# gearshift_controller.net
KiCad netlist of a schematic drawn in EAGLE
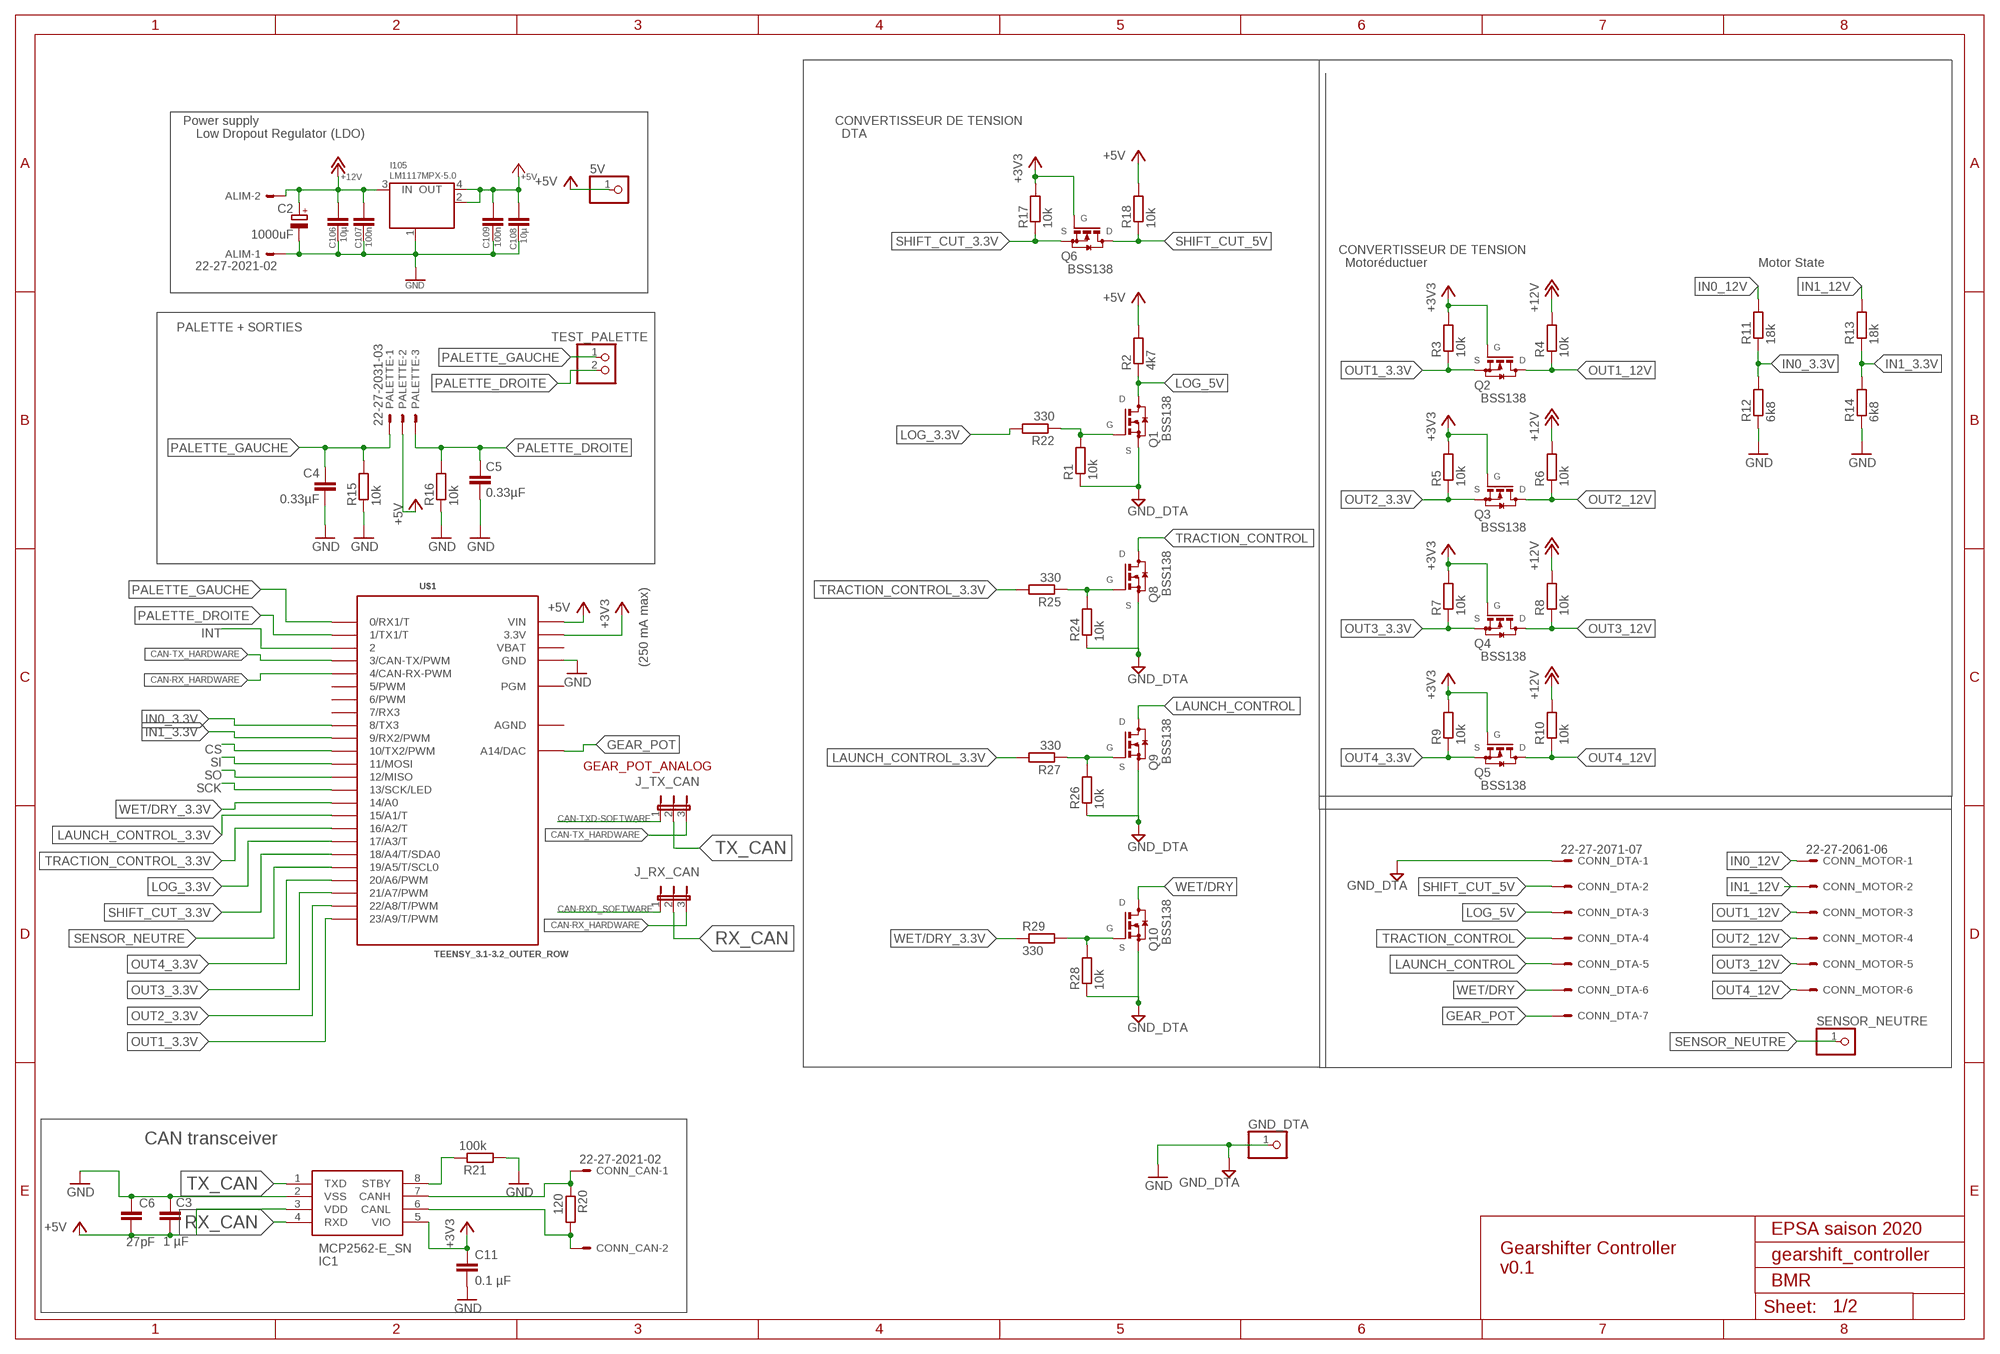
[diagram p0: schematic, sheet 1]
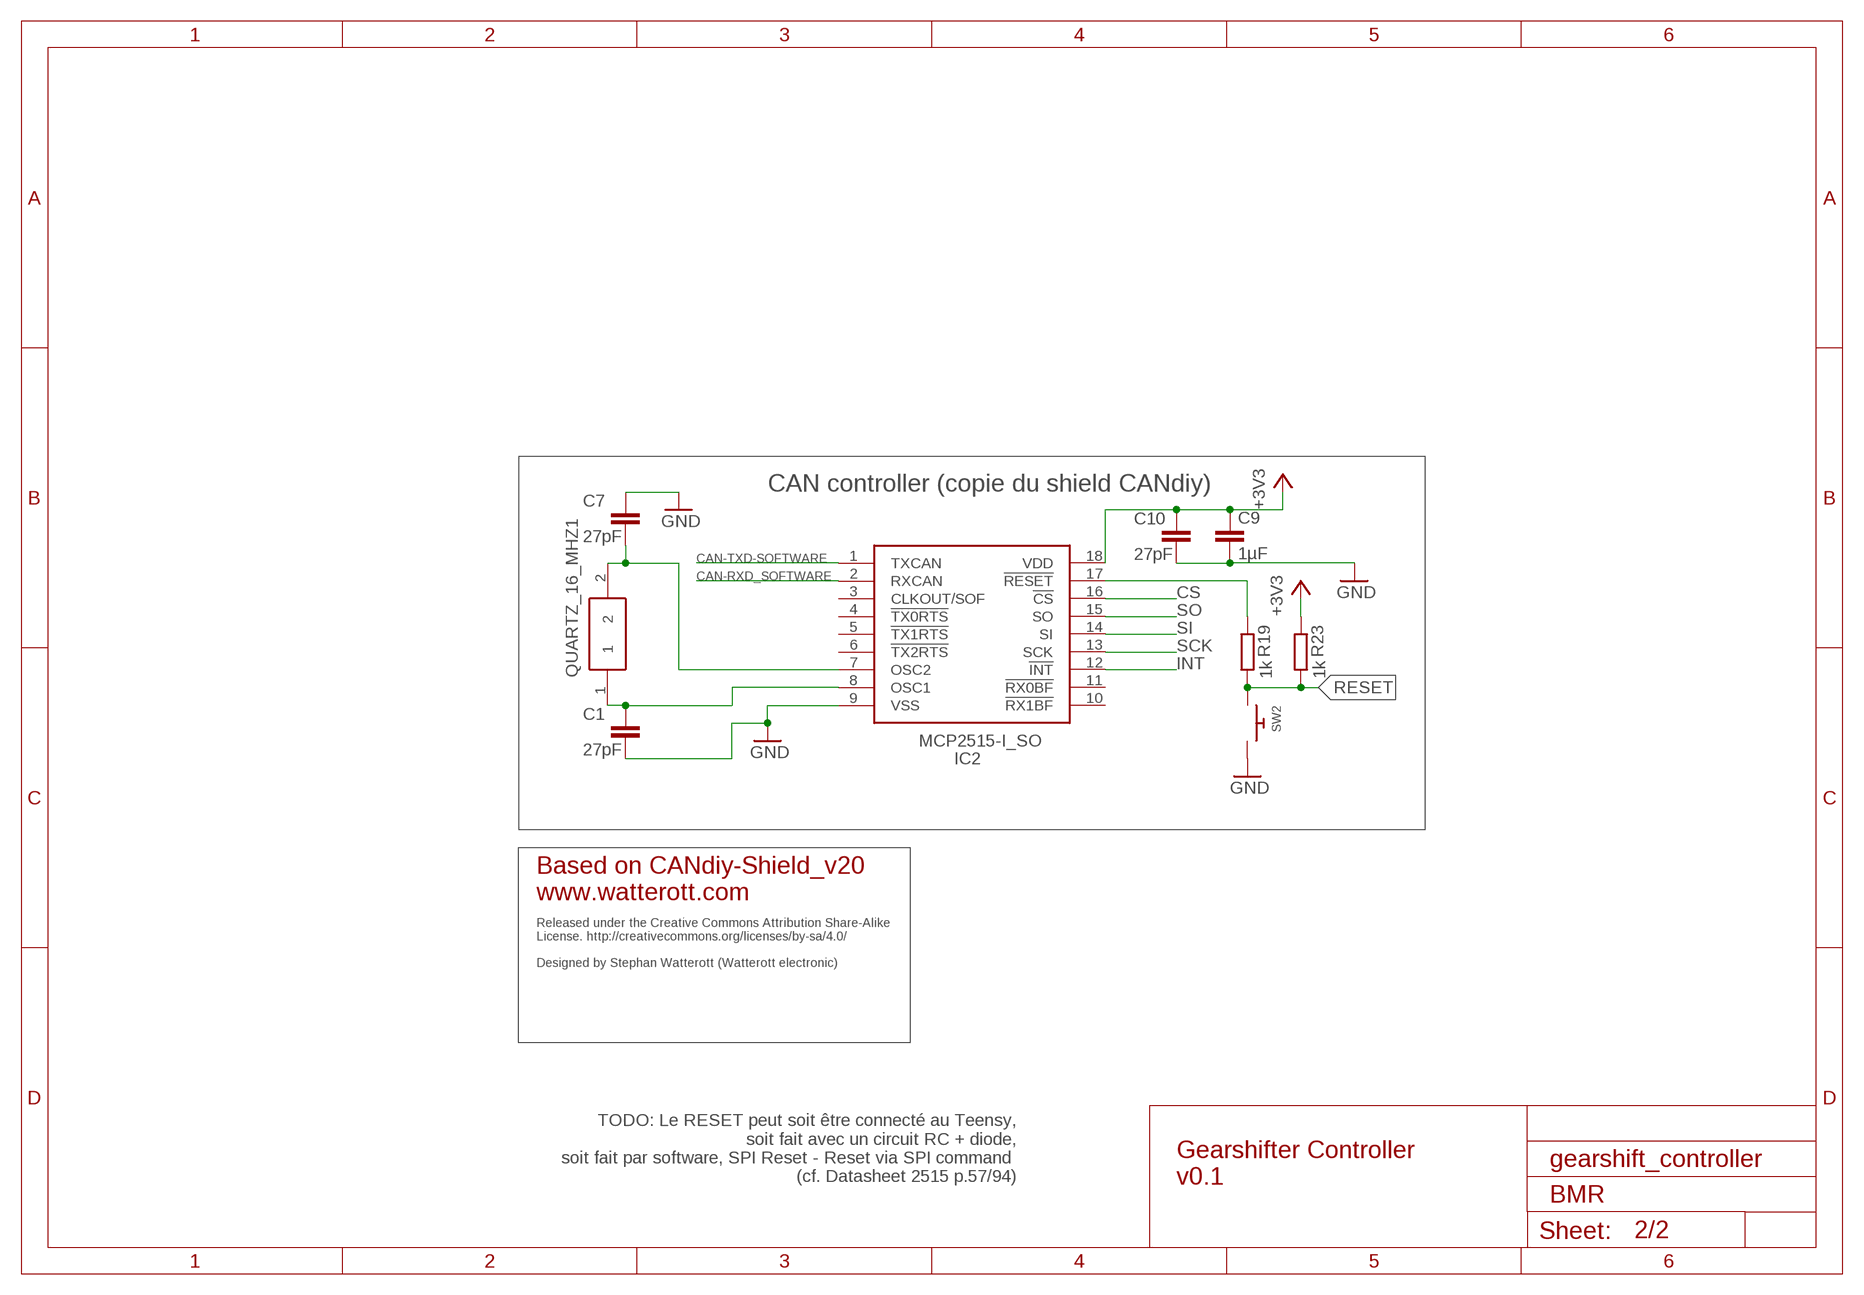
[diagram p1: schematic, sheet 2]

(export (version "E")
  (design (tool "Eeschema 10.0.6"))
  (components
    (comp (ref "C1")
      (value "27pF")
      (footprint "eagle-import:C0805")
      (libsource (lib "eagle-import") (part "rcl_334_C-EUC0805"))
    )
    (comp (ref "C7")
      (value "27pF")
      (footprint "eagle-import:C0805")
      (libsource (lib "eagle-import") (part "rcl_334_C-EUC0805"))
    )
    (comp (ref "C9")
      (value "1µF")
      (footprint "eagle-import:C0805")
      (libsource (lib "eagle-import") (part "rcl_334_C-EUC0805"))
    )
    (comp (ref "C10")
      (value "27pF")
      (footprint "eagle-import:C0805")
      (libsource (lib "eagle-import") (part "rcl_334_C-EUC0805"))
    )
    (comp (ref "IC2")
      (value "MCP2515-I_SO")
      (footprint "eagle-import:SOIC127P1030X265-18N")
      (fields
        (field (name "MANUFACTURER_PART_NUMBER") "MCP2515-I/SO")
        (field (name "RS_PART_NUMBER") "1445765")
      )
      (libsource (lib "eagle-import") (part "MCP2515-I_SO"))
    )
    (comp (ref "QUARTZ_16_MHZ1")
      (value "FOXSLF_160-20")
      (footprint "eagle-import:HC49SLF_1")
      (fields
        (field (name "MANUFACTURER_PART_NUMBER") "FOXSLF/160-20")
        (field (name "RS_PART_NUMBER") "1734298")
      )
      (libsource (lib "eagle-import") (part "FOXSLF_160-20"))
    )
    (comp (ref "R19")
      (value "1k")
      (footprint "eagle-import:R0805")
      (libsource (lib "eagle-import") (part "R-EU_R0805"))
    )
    (comp (ref "R23")
      (value "1k")
      (footprint "eagle-import:R0805")
      (libsource (lib "eagle-import") (part "R-EU_R0805"))
    )
    (comp (ref "SW2")
      (value "SWITCH_PUSHBUTTONEVQ-PE")
      (footprint "eagle-import:TACT_PANA-EVQ")
      (libsource (lib "eagle-import") (part "SWITCH_PUSHBUTTONEVQ-PE"))
    )
    (comp (ref "5V")
      (value "PINHD-1X1")
      (footprint "eagle-import:1X01")
      (libsource (lib "eagle-import") (part "PINHD-1X1"))
    )
    (comp (ref "ALIM")
      (value "22-27-2021-02")
      (footprint "eagle-import:6410-02")
      (fields (field (name "MF") "MOLEX"))
      (libsource (lib "eagle-import") (part "22-?-0227-2021"))
    )
    (comp (ref "C2")
      (value "1000uF")
      (footprint "eagle-import:E25-10")
      (libsource (lib "eagle-import") (part "CPOL-EUE25-10AXIAL"))
    )
    (comp (ref "C3")
      (value "1 µF")
      (footprint "eagle-import:C0805")
      (libsource (lib "eagle-import") (part "rcl_334_C-EUC0805"))
    )
    (comp (ref "C4")
      (value "0.33µF")
      (footprint "eagle-import:C0805")
      (libsource (lib "eagle-import") (part "rcl_334_C-EUC0805"))
    )
    (comp (ref "C5")
      (value "0.33µF")
      (footprint "eagle-import:C0805")
      (libsource (lib "eagle-import") (part "rcl_334_C-EUC0805"))
    )
    (comp (ref "C6")
      (value "27pF")
      (footprint "eagle-import:C0805")
      (libsource (lib "eagle-import") (part "rcl_334_C-EUC0805"))
    )
    (comp (ref "C11")
      (value "0.1 µF")
      (footprint "eagle-import:C0805")
      (libsource (lib "eagle-import") (part "rcl_334_C-EUC0805"))
    )
    (comp (ref "C106")
      (value "10µ")
      (footprint "eagle-import:C0805")
      (libsource (lib "eagle-import") (part "rcl_334_C-EUC0805"))
    )
    (comp (ref "C107")
      (value "100n")
      (footprint "eagle-import:C0603")
      (libsource (lib "eagle-import") (part "C-EUC0603"))
    )
    (comp (ref "C108")
      (value "10µ")
      (footprint "eagle-import:C0805")
      (libsource (lib "eagle-import") (part "rcl_334_C-EUC0805"))
    )
    (comp (ref "C109")
      (value "100n")
      (footprint "eagle-import:C0603")
      (libsource (lib "eagle-import") (part "C-EUC0603"))
    )
    (comp (ref "CONN_CAN")
      (value "22-27-2021-02")
      (footprint "eagle-import:6410-02")
      (fields (field (name "MF") "MOLEX"))
      (libsource (lib "eagle-import") (part "22-?-0227-2021"))
    )
    (comp (ref "CONN_DTA")
      (value "22-27-2071-07")
      (footprint "eagle-import:6410-07")
      (fields (field (name "MF") "MOLEX"))
      (libsource (lib "eagle-import") (part "22-?-0727-2071"))
    )
    (comp (ref "CONN_MOTOR")
      (value "22-27-2061-06")
      (footprint "eagle-import:6410-06")
      (fields (field (name "MF") "MOLEX"))
      (libsource (lib "eagle-import") (part "22-?-0627-2061"))
    )
    (comp (ref "GND_DTA")
      (value "PINHD-1X1")
      (footprint "eagle-import:1X01")
      (libsource (lib "eagle-import") (part "PINHD-1X1"))
    )
    (comp (ref "I105")
      (value "LM1117MPX-5.0")
      (footprint "eagle-import:LINEAR_SOT223")
      (fields (field (name "PART_NUMBER") "LM1117IMPX-5.0"))
      (libsource (lib "eagle-import") (part "0022_LM1117IMPX-5.0"))
    )
    (comp (ref "IC1")
      (value "MCP2562-E_SN")
      (footprint "eagle-import:SOIC127P600X175-8N")
      (fields
        (field (name "MANUFACTURER_PART_NUMBER") "MCP2562-E/SN")
        (field (name "RS_PART_NUMBER") "7990228P")
      )
      (libsource (lib "eagle-import") (part "MCP2562-E_SN"))
    )
    (comp (ref "J_RX_CAN")
      (value "JP2E")
      (footprint "eagle-import:JP2")
      (libsource (lib "eagle-import") (part "JP2E"))
    )
    (comp (ref "J_TX_CAN")
      (value "JP2E")
      (footprint "eagle-import:JP2")
      (libsource (lib "eagle-import") (part "JP2E"))
    )
    (comp (ref "PALETTE")
      (value "22-27-2031-03")
      (footprint "eagle-import:6410-03")
      (fields (field (name "MF") "MOLEX"))
      (libsource (lib "eagle-import") (part "22-?-0327-2031"))
    )
    (comp (ref "Q1")
      (value "BSS138")
      (footprint "eagle-import:SOT23")
      (libsource (lib "eagle-import") (part "BSS123"))
    )
    (comp (ref "Q2")
      (value "BSS138")
      (footprint "eagle-import:SOT23")
      (libsource (lib "eagle-import") (part "BSS123"))
    )
    (comp (ref "Q3")
      (value "BSS138")
      (footprint "eagle-import:SOT23")
      (libsource (lib "eagle-import") (part "BSS123"))
    )
    (comp (ref "Q4")
      (value "BSS138")
      (footprint "eagle-import:SOT23")
      (libsource (lib "eagle-import") (part "BSS123"))
    )
    (comp (ref "Q5")
      (value "BSS138")
      (footprint "eagle-import:SOT23")
      (libsource (lib "eagle-import") (part "BSS123"))
    )
    (comp (ref "Q6")
      (value "BSS138")
      (footprint "eagle-import:SOT23")
      (libsource (lib "eagle-import") (part "BSS123"))
    )
    (comp (ref "Q8")
      (value "BSS138")
      (footprint "eagle-import:SOT23")
      (libsource (lib "eagle-import") (part "BSS123"))
    )
    (comp (ref "Q9")
      (value "BSS138")
      (footprint "eagle-import:SOT23")
      (libsource (lib "eagle-import") (part "BSS123"))
    )
    (comp (ref "Q10")
      (value "BSS138")
      (footprint "eagle-import:SOT23")
      (libsource (lib "eagle-import") (part "BSS123"))
    )
    (comp (ref "R1")
      (value "10k")
      (footprint "eagle-import:R0805")
      (libsource (lib "eagle-import") (part "R-EU_R0805"))
    )
    (comp (ref "R2")
      (value "4k7")
      (footprint "eagle-import:R0805")
      (libsource (lib "eagle-import") (part "R-EU_R0805"))
    )
    (comp (ref "R3")
      (value "10k")
      (footprint "eagle-import:R0805")
      (libsource (lib "eagle-import") (part "R-EU_R0805"))
    )
    (comp (ref "R4")
      (value "10k")
      (footprint "eagle-import:R0805")
      (libsource (lib "eagle-import") (part "R-EU_R0805"))
    )
    (comp (ref "R5")
      (value "10k")
      (footprint "eagle-import:R0805")
      (libsource (lib "eagle-import") (part "R-EU_R0805"))
    )
    (comp (ref "R6")
      (value "10k")
      (footprint "eagle-import:R0805")
      (libsource (lib "eagle-import") (part "R-EU_R0805"))
    )
    (comp (ref "R7")
      (value "10k")
      (footprint "eagle-import:R0805")
      (libsource (lib "eagle-import") (part "R-EU_R0805"))
    )
    (comp (ref "R8")
      (value "10k")
      (footprint "eagle-import:R0805")
      (libsource (lib "eagle-import") (part "R-EU_R0805"))
    )
    (comp (ref "R9")
      (value "10k")
      (footprint "eagle-import:R0805")
      (libsource (lib "eagle-import") (part "R-EU_R0805"))
    )
    (comp (ref "R10")
      (value "10k")
      (footprint "eagle-import:R0805")
      (libsource (lib "eagle-import") (part "R-EU_R0805"))
    )
    (comp (ref "R11")
      (value "18k")
      (footprint "eagle-import:R0805")
      (libsource (lib "eagle-import") (part "R-EU_R0805"))
    )
    (comp (ref "R12")
      (value "6k8")
      (footprint "eagle-import:R0805")
      (libsource (lib "eagle-import") (part "R-EU_R0805"))
    )
    (comp (ref "R13")
      (value "18k")
      (footprint "eagle-import:R0805")
      (libsource (lib "eagle-import") (part "R-EU_R0805"))
    )
    (comp (ref "R14")
      (value "6k8")
      (footprint "eagle-import:R0805")
      (libsource (lib "eagle-import") (part "R-EU_R0805"))
    )
    (comp (ref "R15")
      (value "10k")
      (footprint "eagle-import:R0805")
      (libsource (lib "eagle-import") (part "R-EU_R0805"))
    )
    (comp (ref "R16")
      (value "10k")
      (footprint "eagle-import:R0805")
      (libsource (lib "eagle-import") (part "R-EU_R0805"))
    )
    (comp (ref "R17")
      (value "10k")
      (footprint "eagle-import:R0805")
      (libsource (lib "eagle-import") (part "R-EU_R0805"))
    )
    (comp (ref "R18")
      (value "10k")
      (footprint "eagle-import:R0805")
      (libsource (lib "eagle-import") (part "R-EU_R0805"))
    )
    (comp (ref "R20")
      (value "120")
      (footprint "eagle-import:R0805")
      (libsource (lib "eagle-import") (part "R-EU_R0805"))
    )
    (comp (ref "R21")
      (value "100k")
      (footprint "eagle-import:R0805")
      (libsource (lib "eagle-import") (part "R-EU_R0805"))
    )
    (comp (ref "R22")
      (value "330")
      (footprint "eagle-import:R0805")
      (libsource (lib "eagle-import") (part "R-EU_R0805"))
    )
    (comp (ref "R24")
      (value "10k")
      (footprint "eagle-import:R0805")
      (libsource (lib "eagle-import") (part "R-EU_R0805"))
    )
    (comp (ref "R25")
      (value "330")
      (footprint "eagle-import:R0805")
      (libsource (lib "eagle-import") (part "R-EU_R0805"))
    )
    (comp (ref "R26")
      (value "10k")
      (footprint "eagle-import:R0805")
      (libsource (lib "eagle-import") (part "R-EU_R0805"))
    )
    (comp (ref "R27")
      (value "330")
      (footprint "eagle-import:R0805")
      (libsource (lib "eagle-import") (part "R-EU_R0805"))
    )
    (comp (ref "R28")
      (value "10k")
      (footprint "eagle-import:R0805")
      (libsource (lib "eagle-import") (part "R-EU_R0805"))
    )
    (comp (ref "R29")
      (value "330")
      (footprint "eagle-import:R0805")
      (libsource (lib "eagle-import") (part "R-EU_R0805"))
    )
    (comp (ref "SENSOR_NEUTRE")
      (value "PINHD-1X1")
      (footprint "eagle-import:1X01")
      (libsource (lib "eagle-import") (part "PINHD-1X1"))
    )
    (comp (ref "TEST_PALETTE")
      (value "PINHD-1X2")
      (footprint "eagle-import:1X02")
      (libsource (lib "eagle-import") (part "PINHD-1X2"))
    )
    (comp (ref "U$1")
      (value "TEENSY_3.1-3.2_OUTER_ROW")
      (footprint "eagle-import:TEENSY_3.0-3.2&LC_OUTER_ROW")
      (libsource (lib "eagle-import") (part "TEENSY_3.1-3.2_OUTER_ROW"))
    )
  )
  (nets
    (net (code "1") (name "+3V3") (class "Default")
      (node (ref "C10") (pin "1") (pinfunction "1_1") (pintype "passive"))
      (node (ref "C11") (pin "1") (pinfunction "1_1") (pintype "passive"))
      (node (ref "C9") (pin "1") (pinfunction "1_1") (pintype "passive"))
      (node (ref "IC1") (pin "5") (pinfunction "VIO_5") (pintype "bidirectional"))
      (node (ref "IC2") (pin "18") (pinfunction "VDD_18") (pintype "power_in"))
      (node (ref "Q2") (pin "1") (pinfunction "G_1") (pintype "passive"))
      (node (ref "Q3") (pin "1") (pinfunction "G_1") (pintype "passive"))
      (node (ref "Q4") (pin "1") (pinfunction "G_1") (pintype "passive"))
      (node (ref "Q5") (pin "1") (pinfunction "G_1") (pintype "passive"))
      (node (ref "Q6") (pin "1") (pinfunction "G_1") (pintype "passive"))
      (node (ref "R17") (pin "2") (pinfunction "2_2") (pintype "passive"))
      (node (ref "R23") (pin "1") (pinfunction "1_1") (pintype "passive"))
      (node (ref "R3") (pin "2") (pinfunction "2_2") (pintype "passive"))
      (node (ref "R5") (pin "2") (pinfunction "2_2") (pintype "passive"))
      (node (ref "R7") (pin "2") (pinfunction "2_2") (pintype "passive"))
      (node (ref "R9") (pin "2") (pinfunction "2_2") (pintype "passive"))
      (node (ref "U$1") (pin "3.3V") (pinfunction "3.3V_3.3V") (pintype "power_in"))
      (node (ref "U$1") (pin "3.3V1") (pinfunction "3.3V_3.3V1") (pintype "power_in"))
    )
    (net (code "2") (name "+5V") (class "Default")
      (node (ref "5V") (pin "1") (pinfunction "1_1") (pintype "passive"))
      (node (ref "C108") (pin "1") (pinfunction "1_1") (pintype "passive"))
      (node (ref "C109") (pin "2") (pinfunction "2_2") (pintype "passive"))
      (node (ref "C3") (pin "2") (pinfunction "2_2") (pintype "passive"))
      (node (ref "C6") (pin "2") (pinfunction "2_2") (pintype "passive"))
      (node (ref "I105") (pin "2") (pinfunction "OUT_2") (pintype "passive"))
      (node (ref "I105") (pin "4") (pinfunction "OUT_4") (pintype "passive"))
      (node (ref "IC1") (pin "3") (pinfunction "VDD_3") (pintype "bidirectional"))
      (node (ref "PALETTE") (pin "2") (pinfunction "S_2") (pintype "passive"))
      (node (ref "R18") (pin "2") (pinfunction "2_2") (pintype "passive"))
      (node (ref "R2") (pin "2") (pinfunction "2_2") (pintype "passive"))
      (node (ref "U$1") (pin "VIN") (pinfunction "VIN_VIN") (pintype "power_in"))
    )
    (net (code "3") (name "+12V") (class "Default")
      (node (ref "ALIM") (pin "2") (pinfunction "S_2") (pintype "passive"))
      (node (ref "C106") (pin "1") (pinfunction "1_1") (pintype "passive"))
      (node (ref "C107") (pin "1") (pinfunction "1_1") (pintype "passive"))
      (node (ref "C2") (pin "+") (pinfunction "+_+") (pintype "passive"))
      (node (ref "I105") (pin "3") (pinfunction "IN_3") (pintype "input"))
      (node (ref "R10") (pin "2") (pinfunction "2_2") (pintype "passive"))
      (node (ref "R4") (pin "2") (pinfunction "2_2") (pintype "passive"))
      (node (ref "R6") (pin "2") (pinfunction "2_2") (pintype "passive"))
      (node (ref "R8") (pin "2") (pinfunction "2_2") (pintype "passive"))
    )
    (net (code "4") (name "AGND") (class "Default")
      (node (ref "U$1") (pin "AGND") (pinfunction "AGND_AGND") (pintype "power_in"))
    )
    (net (code "5") (name "CAN-RXD_SOFTWARE") (class "Default")
      (node (ref "IC2") (pin "2") (pinfunction "RXCAN_2") (pintype "bidirectional"))
      (node (ref "J_RX_CAN") (pin "1") (pinfunction "1_1") (pintype "passive"))
    )
    (net (code "6") (name "CAN-RX_HARDWARE") (class "Default")
      (node (ref "J_RX_CAN") (pin "3") (pinfunction "3_3") (pintype "passive"))
      (node (ref "U$1") (pin "4") (pinfunction "4/CAN-RX-PWM_4") (pintype "bidirectional"))
    )
    (net (code "7") (name "CAN-TXD-SOFTWARE") (class "Default")
      (node (ref "IC2") (pin "1") (pinfunction "TXCAN_1") (pintype "bidirectional"))
      (node (ref "J_TX_CAN") (pin "1") (pinfunction "1_1") (pintype "passive"))
    )
    (net (code "8") (name "CAN-TX_HARDWARE") (class "Default")
      (node (ref "J_TX_CAN") (pin "3") (pinfunction "3_3") (pintype "passive"))
      (node (ref "U$1") (pin "3") (pinfunction "3/CAN-TX/PWM_3") (pintype "bidirectional"))
    )
    (net (code "9") (name "CS") (class "Default")
      (node (ref "IC2") (pin "16") (pinfunction "~{CS}_16") (pintype "input"))
      (node (ref "U$1") (pin "10") (pinfunction "10/TX2/PWM_10") (pintype "bidirectional"))
    )
    (net (code "10") (name "GEAR_POT") (class "Default")
      (node (ref "CONN_DTA") (pin "7") (pinfunction "S_7") (pintype "passive"))
      (node (ref "U$1") (pin "RESET/DAC") (pinfunction "A14/DAC_RESET/DAC") (pintype "bidirectional"))
    )
    (net (code "11") (name "GND") (class "Default")
      (node (ref "ALIM") (pin "1") (pinfunction "S_1") (pintype "passive"))
      (node (ref "C1") (pin "2") (pinfunction "2_2") (pintype "passive"))
      (node (ref "C10") (pin "2") (pinfunction "2_2") (pintype "passive"))
      (node (ref "C106") (pin "2") (pinfunction "2_2") (pintype "passive"))
      (node (ref "C107") (pin "2") (pinfunction "2_2") (pintype "passive"))
      (node (ref "C108") (pin "2") (pinfunction "2_2") (pintype "passive"))
      (node (ref "C109") (pin "1") (pinfunction "1_1") (pintype "passive"))
      (node (ref "C11") (pin "2") (pinfunction "2_2") (pintype "passive"))
      (node (ref "C2") (pin "-") (pinfunction "-_-") (pintype "passive"))
      (node (ref "C3") (pin "1") (pinfunction "1_1") (pintype "passive"))
      (node (ref "C4") (pin "2") (pinfunction "2_2") (pintype "passive"))
      (node (ref "C5") (pin "2") (pinfunction "2_2") (pintype "passive"))
      (node (ref "C6") (pin "1") (pinfunction "1_1") (pintype "passive"))
      (node (ref "C7") (pin "1") (pinfunction "1_1") (pintype "passive"))
      (node (ref "C9") (pin "2") (pinfunction "2_2") (pintype "passive"))
      (node (ref "CONN_DTA") (pin "1") (pinfunction "S_1") (pintype "passive"))
      (node (ref "GND_DTA") (pin "1") (pinfunction "1_1") (pintype "passive"))
      (node (ref "I105") (pin "1") (pinfunction "GND/ADJ_1") (pintype "input"))
      (node (ref "IC1") (pin "2") (pinfunction "VSS_2") (pintype "bidirectional"))
      (node (ref "IC2") (pin "9") (pinfunction "VSS_9") (pintype "power_in"))
      (node (ref "Q1") (pin "2") (pinfunction "S_2") (pintype "passive"))
      (node (ref "Q10") (pin "2") (pinfunction "S_2") (pintype "passive"))
      (node (ref "Q8") (pin "2") (pinfunction "S_2") (pintype "passive"))
      (node (ref "Q9") (pin "2") (pinfunction "S_2") (pintype "passive"))
      (node (ref "R1") (pin "1") (pinfunction "1_1") (pintype "passive"))
      (node (ref "R12") (pin "1") (pinfunction "1_1") (pintype "passive"))
      (node (ref "R14") (pin "1") (pinfunction "1_1") (pintype "passive"))
      (node (ref "R15") (pin "1") (pinfunction "1_1") (pintype "passive"))
      (node (ref "R16") (pin "1") (pinfunction "1_1") (pintype "passive"))
      (node (ref "R21") (pin "1") (pinfunction "1_1") (pintype "passive"))
      (node (ref "R24") (pin "1") (pinfunction "1_1") (pintype "passive"))
      (node (ref "R26") (pin "1") (pinfunction "1_1") (pintype "passive"))
      (node (ref "R28") (pin "1") (pinfunction "1_1") (pintype "passive"))
      (node (ref "SW2") (pin "P$2") (pinfunction "P$2_P$2") (pintype "passive"))
      (node (ref "U$1") (pin "GND") (pinfunction "GND_GND") (pintype "power_in"))
      (node (ref "U$1") (pin "GND1") (pinfunction "GND_GND1") (pintype "power_in"))
    )
    (net (code "12") (name "IN0_3.3V") (class "Default")
      (node (ref "R11") (pin "1") (pinfunction "1_1") (pintype "passive"))
      (node (ref "R12") (pin "2") (pinfunction "2_2") (pintype "passive"))
      (node (ref "U$1") (pin "8") (pinfunction "8/TX3_8") (pintype "bidirectional"))
    )
    (net (code "13") (name "IN0_12V") (class "Default")
      (node (ref "CONN_MOTOR") (pin "1") (pinfunction "S_1") (pintype "passive"))
      (node (ref "R11") (pin "2") (pinfunction "2_2") (pintype "passive"))
    )
    (net (code "14") (name "IN1_3.3V") (class "Default")
      (node (ref "R13") (pin "1") (pinfunction "1_1") (pintype "passive"))
      (node (ref "R14") (pin "2") (pinfunction "2_2") (pintype "passive"))
      (node (ref "U$1") (pin "9") (pinfunction "9/RX2/PWM_9") (pintype "bidirectional"))
    )
    (net (code "15") (name "IN1_12V") (class "Default")
      (node (ref "CONN_MOTOR") (pin "2") (pinfunction "S_2") (pintype "passive"))
      (node (ref "R13") (pin "2") (pinfunction "2_2") (pintype "passive"))
    )
    (net (code "16") (name "INT") (class "Default")
      (node (ref "IC2") (pin "12") (pinfunction "~{INT}_12") (pintype "input"))
      (node (ref "U$1") (pin "2") (pinfunction "2_2") (pintype "bidirectional"))
    )
    (net (code "17") (name "LAUNCH_CONTROL") (class "Default")
      (node (ref "CONN_DTA") (pin "5") (pinfunction "S_5") (pintype "passive"))
      (node (ref "Q9") (pin "3") (pinfunction "D_3") (pintype "passive"))
    )
    (net (code "18") (name "LAUNCH_CONTROL_3.3V") (class "Default")
      (node (ref "R27") (pin "2") (pinfunction "2_2") (pintype "passive"))
      (node (ref "U$1") (pin "15/A1") (pinfunction "15/A1/T_15/A1") (pintype "bidirectional"))
    )
    (net (code "19") (name "LOG_3.3V") (class "Default")
      (node (ref "R22") (pin "2") (pinfunction "2_2") (pintype "passive"))
      (node (ref "U$1") (pin "17/A3") (pinfunction "17/A3/T_17/A3") (pintype "bidirectional"))
    )
    (net (code "20") (name "LOG_5V") (class "Default")
      (node (ref "CONN_DTA") (pin "3") (pinfunction "S_3") (pintype "passive"))
      (node (ref "Q1") (pin "3") (pinfunction "D_3") (pintype "passive"))
      (node (ref "R2") (pin "1") (pinfunction "1_1") (pintype "passive"))
    )
    (net (code "21") (name "Net-(CONN_CANA-S)") (class "Default")
      (node (ref "CONN_CAN") (pin "1") (pinfunction "S_1") (pintype "passive"))
      (node (ref "IC1") (pin "7") (pinfunction "CANH_7") (pintype "bidirectional"))
      (node (ref "R20") (pin "1") (pinfunction "1_1") (pintype "passive"))
    )
    (net (code "22") (name "Net-(CONN_CANB-S)") (class "Default")
      (node (ref "CONN_CAN") (pin "2") (pinfunction "S_2") (pintype "passive"))
      (node (ref "IC1") (pin "6") (pinfunction "CANL_6") (pintype "bidirectional"))
      (node (ref "R20") (pin "2") (pinfunction "2_2") (pintype "passive"))
    )
    (net (code "23") (name "Net-(IC1-STBY)") (class "Default")
      (node (ref "IC1") (pin "8") (pinfunction "STBY_8") (pintype "bidirectional"))
      (node (ref "R21") (pin "2") (pinfunction "2_2") (pintype "passive"))
    )
    (net (code "24") (name "Net-(IC2-OSC1)") (class "Default")
      (node (ref "C1") (pin "1") (pinfunction "1_1") (pintype "passive"))
      (node (ref "IC2") (pin "8") (pinfunction "OSC1_8") (pintype "bidirectional"))
      (node (ref "QUARTZ_16_MHZ1") (pin "1") (pinfunction "1_1") (pintype "bidirectional"))
    )
    (net (code "25") (name "Net-(IC2-OSC2)") (class "Default")
      (node (ref "C7") (pin "2") (pinfunction "2_2") (pintype "passive"))
      (node (ref "IC2") (pin "7") (pinfunction "OSC2_7") (pintype "bidirectional"))
      (node (ref "QUARTZ_16_MHZ1") (pin "2") (pinfunction "2_2") (pintype "bidirectional"))
    )
    (net (code "26") (name "Net-(IC2-~{RESET})") (class "Default")
      (node (ref "IC2") (pin "17") (pinfunction "~{RESET}_17") (pintype "bidirectional"))
      (node (ref "R19") (pin "1") (pinfunction "1_1") (pintype "passive"))
    )
    (net (code "27") (name "Net-(Q1-G)") (class "Default")
      (node (ref "Q1") (pin "1") (pinfunction "G_1") (pintype "passive"))
      (node (ref "R1") (pin "2") (pinfunction "2_2") (pintype "passive"))
      (node (ref "R22") (pin "1") (pinfunction "1_1") (pintype "passive"))
    )
    (net (code "28") (name "Net-(Q8-G)") (class "Default")
      (node (ref "Q8") (pin "1") (pinfunction "G_1") (pintype "passive"))
      (node (ref "R24") (pin "2") (pinfunction "2_2") (pintype "passive"))
      (node (ref "R25") (pin "1") (pinfunction "1_1") (pintype "passive"))
    )
    (net (code "29") (name "Net-(Q9-G)") (class "Default")
      (node (ref "Q9") (pin "1") (pinfunction "G_1") (pintype "passive"))
      (node (ref "R26") (pin "2") (pinfunction "2_2") (pintype "passive"))
      (node (ref "R27") (pin "1") (pinfunction "1_1") (pintype "passive"))
    )
    (net (code "30") (name "Net-(Q10-G)") (class "Default")
      (node (ref "Q10") (pin "1") (pinfunction "G_1") (pintype "passive"))
      (node (ref "R28") (pin "2") (pinfunction "2_2") (pintype "passive"))
      (node (ref "R29") (pin "2") (pinfunction "2_2") (pintype "passive"))
    )
    (net (code "31") (name "OUT1_3.3V") (class "Default")
      (node (ref "Q2") (pin "2") (pinfunction "S_2") (pintype "passive"))
      (node (ref "R3") (pin "1") (pinfunction "1_1") (pintype "passive"))
      (node (ref "U$1") (pin "23/A9") (pinfunction "23/A9/T/PWM_23/A9") (pintype "bidirectional"))
    )
    (net (code "32") (name "OUT1_12V") (class "Default")
      (node (ref "CONN_MOTOR") (pin "3") (pinfunction "S_3") (pintype "passive"))
      (node (ref "Q2") (pin "3") (pinfunction "D_3") (pintype "passive"))
      (node (ref "R4") (pin "1") (pinfunction "1_1") (pintype "passive"))
    )
    (net (code "33") (name "OUT2_3.3V") (class "Default")
      (node (ref "Q3") (pin "2") (pinfunction "S_2") (pintype "passive"))
      (node (ref "R5") (pin "1") (pinfunction "1_1") (pintype "passive"))
      (node (ref "U$1") (pin "22/A8") (pinfunction "22/A8/T/PWM_22/A8") (pintype "bidirectional"))
    )
    (net (code "34") (name "OUT2_12V") (class "Default")
      (node (ref "CONN_MOTOR") (pin "4") (pinfunction "S_4") (pintype "passive"))
      (node (ref "Q3") (pin "3") (pinfunction "D_3") (pintype "passive"))
      (node (ref "R6") (pin "1") (pinfunction "1_1") (pintype "passive"))
    )
    (net (code "35") (name "OUT3_3.3V") (class "Default")
      (node (ref "Q4") (pin "2") (pinfunction "S_2") (pintype "passive"))
      (node (ref "R7") (pin "1") (pinfunction "1_1") (pintype "passive"))
      (node (ref "U$1") (pin "21/A7") (pinfunction "21/A7/PWM_21/A7") (pintype "bidirectional"))
    )
    (net (code "36") (name "OUT3_12V") (class "Default")
      (node (ref "CONN_MOTOR") (pin "5") (pinfunction "S_5") (pintype "passive"))
      (node (ref "Q4") (pin "3") (pinfunction "D_3") (pintype "passive"))
      (node (ref "R8") (pin "1") (pinfunction "1_1") (pintype "passive"))
    )
    (net (code "37") (name "OUT4_3.3V") (class "Default")
      (node (ref "Q5") (pin "2") (pinfunction "S_2") (pintype "passive"))
      (node (ref "R9") (pin "1") (pinfunction "1_1") (pintype "passive"))
      (node (ref "U$1") (pin "20/A6") (pinfunction "20/A6/PWM_20/A6") (pintype "bidirectional"))
    )
    (net (code "38") (name "OUT4_12V") (class "Default")
      (node (ref "CONN_MOTOR") (pin "6") (pinfunction "S_6") (pintype "passive"))
      (node (ref "Q5") (pin "3") (pinfunction "D_3") (pintype "passive"))
      (node (ref "R10") (pin "1") (pinfunction "1_1") (pintype "passive"))
    )
    (net (code "39") (name "PALETTE_DROITE") (class "Default")
      (node (ref "C5") (pin "1") (pinfunction "1_1") (pintype "passive"))
      (node (ref "PALETTE") (pin "3") (pinfunction "S_3") (pintype "passive"))
      (node (ref "R16") (pin "2") (pinfunction "2_2") (pintype "passive"))
      (node (ref "TEST_PALETTE") (pin "2") (pinfunction "2_2") (pintype "passive"))
      (node (ref "U$1") (pin "1") (pinfunction "1/TX1/T_1") (pintype "bidirectional"))
    )
    (net (code "40") (name "PALETTE_GAUCHE") (class "Default")
      (node (ref "C4") (pin "1") (pinfunction "1_1") (pintype "passive"))
      (node (ref "PALETTE") (pin "1") (pinfunction "S_1") (pintype "passive"))
      (node (ref "R15") (pin "2") (pinfunction "2_2") (pintype "passive"))
      (node (ref "TEST_PALETTE") (pin "1") (pinfunction "1_1") (pintype "passive"))
      (node (ref "U$1") (pin "0") (pinfunction "0/RX1/T_0") (pintype "bidirectional"))
    )
    (net (code "41") (name "RESET") (class "Default")
      (node (ref "R19") (pin "2") (pinfunction "2_2") (pintype "passive"))
      (node (ref "R23") (pin "2") (pinfunction "2_2") (pintype "passive"))
      (node (ref "SW2") (pin "P$1") (pinfunction "P$1_P$1") (pintype "passive"))
    )
    (net (code "42") (name "RX_CAN") (class "Default")
      (node (ref "IC1") (pin "4") (pinfunction "RXD_4") (pintype "bidirectional"))
      (node (ref "J_RX_CAN") (pin "2") (pinfunction "2_2") (pintype "passive"))
    )
    (net (code "43") (name "SCK") (class "Default")
      (node (ref "IC2") (pin "13") (pinfunction "SCK_13") (pintype "bidirectional"))
      (node (ref "U$1") (pin "13") (pinfunction "13/SCK/LED_13") (pintype "bidirectional"))
    )
    (net (code "44") (name "SENSOR_NEUTRE") (class "Default")
      (node (ref "SENSOR_NEUTRE") (pin "1") (pinfunction "1_1") (pintype "passive"))
      (node (ref "U$1") (pin "19/A5") (pinfunction "19/A5/T/SCL0_19/A5") (pintype "bidirectional"))
    )
    (net (code "45") (name "SHIFT_CUT_3.3V") (class "Default")
      (node (ref "Q6") (pin "2") (pinfunction "S_2") (pintype "passive"))
      (node (ref "R17") (pin "1") (pinfunction "1_1") (pintype "passive"))
      (node (ref "U$1") (pin "18/A4") (pinfunction "18/A4/T/SDA0_18/A4") (pintype "bidirectional"))
    )
    (net (code "46") (name "SHIFT_CUT_5V") (class "Default")
      (node (ref "CONN_DTA") (pin "2") (pinfunction "S_2") (pintype "passive"))
      (node (ref "Q6") (pin "3") (pinfunction "D_3") (pintype "passive"))
      (node (ref "R18") (pin "1") (pinfunction "1_1") (pintype "passive"))
    )
    (net (code "47") (name "SI") (class "Default")
      (node (ref "IC2") (pin "14") (pinfunction "SI_14") (pintype "bidirectional"))
      (node (ref "U$1") (pin "11") (pinfunction "11/MOSI_11") (pintype "bidirectional"))
    )
    (net (code "48") (name "SO") (class "Default")
      (node (ref "IC2") (pin "15") (pinfunction "SO_15") (pintype "bidirectional"))
      (node (ref "U$1") (pin "12") (pinfunction "12/MISO_12") (pintype "bidirectional"))
    )
    (net (code "49") (name "TRACTION_CONTROL") (class "Default")
      (node (ref "CONN_DTA") (pin "4") (pinfunction "S_4") (pintype "passive"))
      (node (ref "Q8") (pin "3") (pinfunction "D_3") (pintype "passive"))
    )
    (net (code "50") (name "TRACTION_CONTROL_3.3V") (class "Default")
      (node (ref "R25") (pin "2") (pinfunction "2_2") (pintype "passive"))
      (node (ref "U$1") (pin "16/A2") (pinfunction "16/A2/T_16/A2") (pintype "bidirectional"))
    )
    (net (code "51") (name "TX_CAN") (class "Default")
      (node (ref "IC1") (pin "1") (pinfunction "TXD_1") (pintype "bidirectional"))
      (node (ref "J_TX_CAN") (pin "2") (pinfunction "2_2") (pintype "passive"))
    )
    (net (code "52") (name "VBAT") (class "Default")
      (node (ref "U$1") (pin "VBAT") (pinfunction "VBAT_VBAT") (pintype "power_in"))
    )
    (net (code "53") (name "WET{slash}DRY") (class "Default")
      (node (ref "CONN_DTA") (pin "6") (pinfunction "S_6") (pintype "passive"))
      (node (ref "Q10") (pin "3") (pinfunction "D_3") (pintype "passive"))
    )
    (net (code "54") (name "WET{slash}DRY_3.3V") (class "Default")
      (node (ref "R29") (pin "1") (pinfunction "1_1") (pintype "passive"))
      (node (ref "U$1") (pin "14/A0") (pinfunction "14/A0_14/A0") (pintype "bidirectional"))
    )
    (net (code "55") (name "unconnected-(IC2-CLKOUT{slash}SOF-Pad3)") (class "Default")
      (node (ref "IC2") (pin "3") (pinfunction "CLKOUT/SOF_3") (pintype "output"))
    )
    (net (code "56") (name "unconnected-(IC2-~{RX0BF}-Pad11)") (class "Default")
      (node (ref "IC2") (pin "11") (pinfunction "~{RX0BF}_11") (pintype "bidirectional"))
    )
    (net (code "57") (name "unconnected-(IC2-~{RX1BF}-Pad10)") (class "Default")
      (node (ref "IC2") (pin "10") (pinfunction "~{RX1BF}_10") (pintype "bidirectional"))
    )
    (net (code "58") (name "unconnected-(IC2-~{TX0RTS}-Pad4)") (class "Default")
      (node (ref "IC2") (pin "4") (pinfunction "~{TX0RTS}_4") (pintype "bidirectional"))
    )
    (net (code "59") (name "unconnected-(IC2-~{TX1RTS}-Pad5)") (class "Default")
      (node (ref "IC2") (pin "5") (pinfunction "~{TX1RTS}_5") (pintype "bidirectional"))
    )
    (net (code "60") (name "unconnected-(IC2-~{TX2RTS}-Pad6)") (class "Default")
      (node (ref "IC2") (pin "6") (pinfunction "~{TX2RTS}_6") (pintype "bidirectional"))
    )
    (net (code "61") (name "unconnected-(U$1-5{slash}PWM-Pad5)") (class "Default")
      (node (ref "U$1") (pin "5") (pinfunction "5/PWM_5") (pintype "bidirectional"))
    )
    (net (code "62") (name "unconnected-(U$1-6{slash}PWM-Pad6)") (class "Default")
      (node (ref "U$1") (pin "6") (pinfunction "6/PWM_6") (pintype "bidirectional"))
    )
    (net (code "63") (name "unconnected-(U$1-7{slash}RX3-Pad7)") (class "Default")
      (node (ref "U$1") (pin "7") (pinfunction "7/RX3_7") (pintype "bidirectional"))
    )
    (net (code "64") (name "unconnected-(U$1-PadPGM)") (class "Default")
      (node (ref "U$1") (pin "PGM") (pinfunction "PGM_PGM") (pintype "bidirectional"))
    )
  )
)
